# Main.net
KiCad netlist of a schematic drawn in Altium Designer
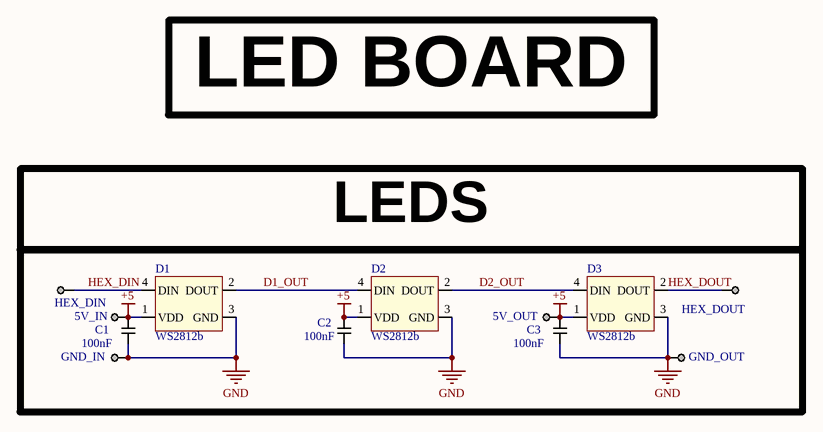
[diagram p0: Main.SchDoc]

(export (version "E")
  (design (tool "Eeschema 10.0.6"))
  (components
    (comp (ref "5V_IN")
      (value "18 AWG Hole")
      (footprint "18 AWG Hole")
      (libsource (lib "smLib") (part "18 AWG Hole"))
    )
    (comp (ref "5V_OUT")
      (value "18 AWG Hole")
      (footprint "18 AWG Hole")
      (libsource (lib "smLib") (part "18 AWG Hole"))
    )
    (comp (ref "C1")
      (value "100nF")
      (footprint "CAP_0805_HIGH")
      (description "0805 Capacitor")
      (libsource (lib "smLib") (part "Capacitor_0805"))
    )
    (comp (ref "C2")
      (value "100nF")
      (footprint "CAP_0805_HIGH")
      (description "0805 Capacitor")
      (libsource (lib "smLib") (part "Capacitor_0805"))
    )
    (comp (ref "C3")
      (value "100nF")
      (footprint "CAP_0805_HIGH")
      (description "0805 Capacitor")
      (libsource (lib "smLib") (part "Capacitor_0805"))
    )
    (comp (ref "D1")
      (value "WS2812b")
      (footprint "WS2812b")
      (description "WS2812b LED RGB")
      (libsource (lib "smLib") (part "WS2812b"))
    )
    (comp (ref "D2")
      (value "WS2812b")
      (footprint "WS2812b")
      (description "WS2812b LED RGB")
      (libsource (lib "smLib") (part "WS2812b"))
    )
    (comp (ref "D3")
      (value "WS2812b")
      (footprint "WS2812b")
      (description "WS2812b LED RGB")
      (libsource (lib "smLib") (part "WS2812b"))
    )
    (comp (ref "GND_IN")
      (value "18 AWG Hole")
      (footprint "18 AWG Hole")
      (libsource (lib "smLib") (part "18 AWG Hole"))
    )
    (comp (ref "GND_OUT")
      (value "18 AWG Hole")
      (footprint "18 AWG Hole")
      (libsource (lib "smLib") (part "18 AWG Hole"))
    )
    (comp (ref "HEX_DIN")
      (value "18 AWG Hole")
      (footprint "18 AWG Hole")
      (libsource (lib "smLib") (part "18 AWG Hole"))
    )
    (comp (ref "HEX_DOUT")
      (value "18 AWG Hole")
      (footprint "18 AWG Hole")
      (libsource (lib "smLib") (part "18 AWG Hole"))
    )
  )
  (nets
    (net (code "1") (name "+5") (class "Default")
      (node (ref "5V_IN") (pin "1") (pinfunction "1_1") (pintype "passive"))
      (node (ref "5V_OUT") (pin "1") (pinfunction "1_1") (pintype "passive"))
      (node (ref "C1") (pin "2") (pinfunction "2_2") (pintype "passive"))
      (node (ref "C2") (pin "2") (pinfunction "2_2") (pintype "passive"))
      (node (ref "C3") (pin "2") (pinfunction "2_2") (pintype "passive"))
      (node (ref "D1") (pin "1") (pinfunction "VDD_1") (pintype "passive"))
      (node (ref "D2") (pin "1") (pinfunction "VDD_1") (pintype "passive"))
      (node (ref "D3") (pin "1") (pinfunction "VDD_1") (pintype "passive"))
    )
    (net (code "2") (name "/D1_OUT") (class "Default")
      (node (ref "D1") (pin "2") (pinfunction "DOUT_2") (pintype "passive"))
      (node (ref "D2") (pin "4") (pinfunction "DIN_4") (pintype "passive"))
    )
    (net (code "3") (name "/D2_OUT") (class "Default")
      (node (ref "D2") (pin "2") (pinfunction "DOUT_2") (pintype "passive"))
      (node (ref "D3") (pin "4") (pinfunction "DIN_4") (pintype "passive"))
    )
    (net (code "4") (name "/HEX_DIN") (class "Default")
      (node (ref "D1") (pin "4") (pinfunction "DIN_4") (pintype "passive"))
      (node (ref "HEX_DIN") (pin "1") (pinfunction "1_1") (pintype "passive"))
    )
    (net (code "5") (name "/HEX_DOUT") (class "Default")
      (node (ref "D3") (pin "2") (pinfunction "DOUT_2") (pintype "passive"))
      (node (ref "HEX_DOUT") (pin "1") (pinfunction "1_1") (pintype "passive"))
    )
    (net (code "6") (name "GND") (class "Default")
      (node (ref "C1") (pin "1") (pinfunction "1_1") (pintype "passive"))
      (node (ref "C2") (pin "1") (pinfunction "1_1") (pintype "passive"))
      (node (ref "C3") (pin "1") (pinfunction "1_1") (pintype "passive"))
      (node (ref "D1") (pin "3") (pinfunction "GND_3") (pintype "passive"))
      (node (ref "D2") (pin "3") (pinfunction "GND_3") (pintype "passive"))
      (node (ref "D3") (pin "3") (pinfunction "GND_3") (pintype "passive"))
      (node (ref "GND_IN") (pin "1") (pinfunction "1_1") (pintype "passive"))
      (node (ref "GND_OUT") (pin "1") (pinfunction "1_1") (pintype "passive"))
    )
  )
)
